# universal_flech.net
KiCad netlist of a schematic drawn in Altium Designer
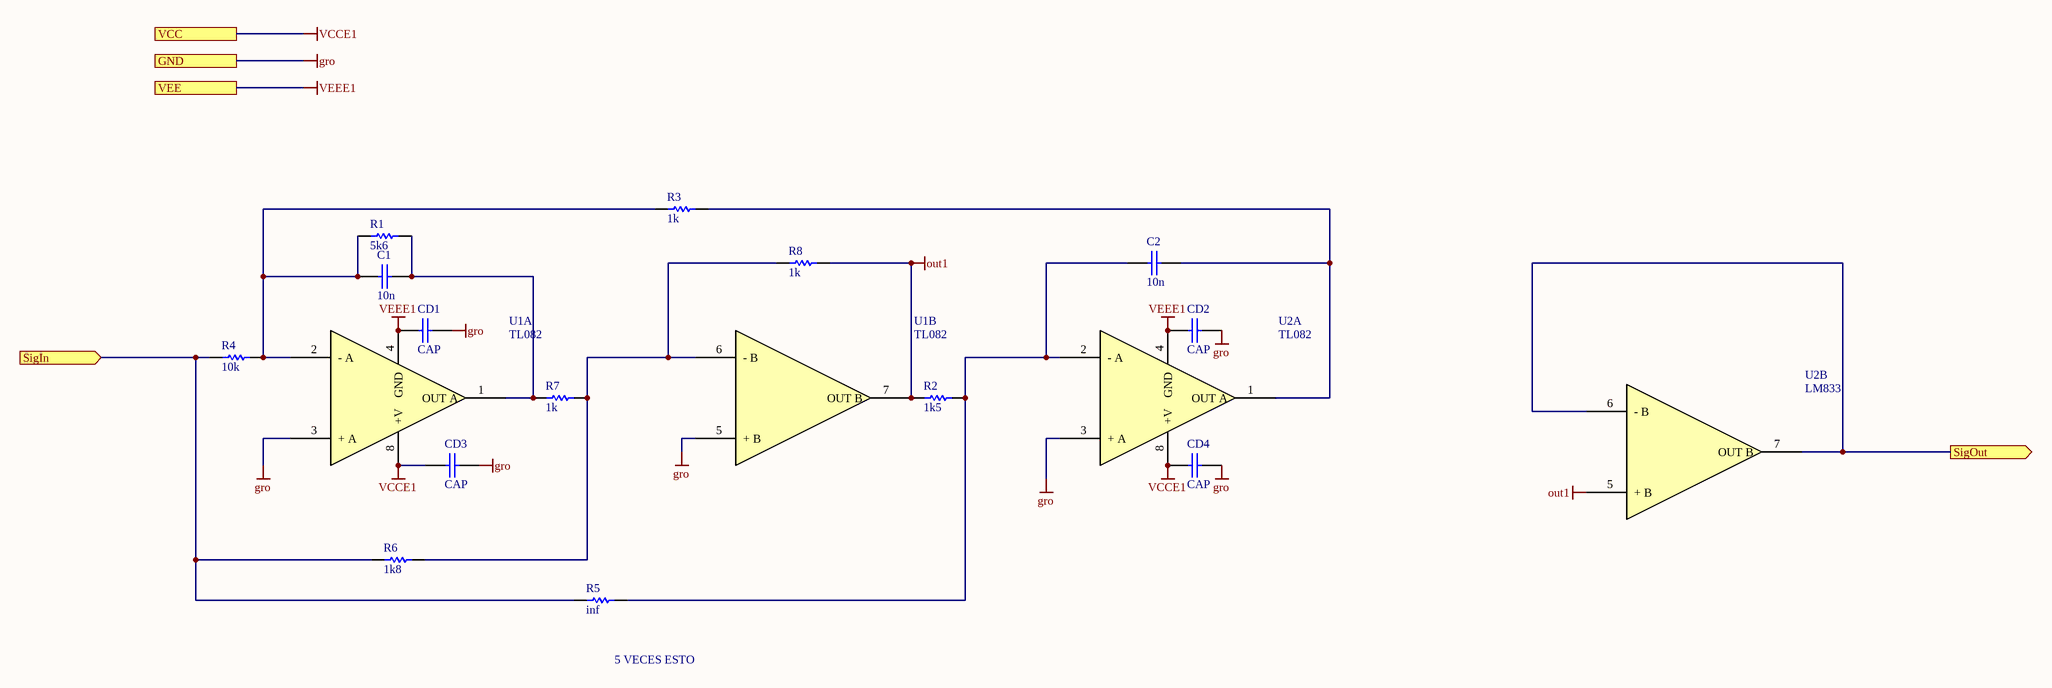
[diagram p0: universal_flech.SchDoc]

(export (version "E")
  (design (tool "Eeschema 10.0.6"))
  (components
    (comp (ref "C1") (value "10n") (footprint "CAP200") (libsource (lib "LIBEBAL") (part "CAP")))
    (comp (ref "C2") (value "10n") (footprint "CAP200") (libsource (lib "LIBEBAL") (part "CAP")))
    (comp (ref "CD1") (value "CAP") (footprint "CAP200") (libsource (lib "LIBEBAL") (part "CAP")))
    (comp (ref "CD2") (value "CAP") (footprint "CAP200") (libsource (lib "LIBEBAL") (part "CAP")))
    (comp (ref "CD3") (value "CAP") (footprint "CAP200") (libsource (lib "LIBEBAL") (part "CAP")))
    (comp (ref "CD4") (value "CAP") (footprint "CAP200") (libsource (lib "LIBEBAL") (part "CAP")))
    (comp (ref "R1") (value "5k6") (footprint "0805") (libsource (lib "LIBEBAL") (part "RES")))
    (comp (ref "R2") (value "1k5") (footprint "0805") (libsource (lib "LIBEBAL") (part "RES")))
    (comp (ref "R3") (value "1k") (footprint "0805") (libsource (lib "LIBEBAL") (part "RES")))
    (comp (ref "R4") (value "10k") (footprint "0805") (libsource (lib "LIBEBAL") (part "RES")))
    (comp (ref "R5") (value "inf") (footprint "0805") (libsource (lib "LIBEBAL") (part "RES")))
    (comp (ref "R6") (value "1k8") (footprint "0805") (libsource (lib "LIBEBAL") (part "RES")))
    (comp (ref "R7") (value "1k") (footprint "0805") (libsource (lib "LIBEBAL") (part "RES")))
    (comp (ref "R8") (value "1k") (footprint "0805") (libsource (lib "LIBEBAL") (part "RES")))
    (comp (ref "U1")
      (value "TL082")
      (footprint "DIP8")
      (description "Dual Audio Operational Amplifier")
      (libsource (lib "LIBEBAL") (part "LM833"))
    )
    (comp (ref "U2")
      (value "TL082")
      (footprint "DIP8")
      (description "Dual Audio Operational Amplifier")
      (libsource (lib "LIBEBAL") (part "LM833"))
    )
  )
  (nets
    (net (code "1") (name "/SigIn") (class "Default")
      (node (ref "R4") (pin "1") (pinfunction "1_1") (pintype "passive"))
      (node (ref "R5") (pin "1") (pinfunction "1_1") (pintype "passive"))
      (node (ref "R6") (pin "1") (pinfunction "1_1") (pintype "passive"))
    )
    (net (code "2") (name "/SigOut") (class "Default")
      (node (ref "U2") (pin "6") (pinfunction "-_B_6") (pintype "passive"))
      (node (ref "U2") (pin "7") (pinfunction "OUT_B_7") (pintype "passive"))
    )
    (net (code "3") (name "Net-(U1A--_A)") (class "Default")
      (node (ref "C1") (pin "1") (pinfunction "1_1") (pintype "passive"))
      (node (ref "R1") (pin "1") (pinfunction "1_1") (pintype "passive"))
      (node (ref "R3") (pin "1") (pinfunction "1_1") (pintype "passive"))
      (node (ref "R4") (pin "2") (pinfunction "2_2") (pintype "passive"))
      (node (ref "U1") (pin "2") (pinfunction "-_A_2") (pintype "passive"))
    )
    (net (code "4") (name "Net-(U1A-OUT_A)") (class "Default")
      (node (ref "C1") (pin "2") (pinfunction "2_2") (pintype "passive"))
      (node (ref "R1") (pin "2") (pinfunction "2_2") (pintype "passive"))
      (node (ref "R7") (pin "1") (pinfunction "1_1") (pintype "passive"))
      (node (ref "U1") (pin "1") (pinfunction "OUT_A_1") (pintype "passive"))
    )
    (net (code "5") (name "Net-(U1B--_B)") (class "Default")
      (node (ref "R6") (pin "2") (pinfunction "2_2") (pintype "passive"))
      (node (ref "R7") (pin "2") (pinfunction "2_2") (pintype "passive"))
      (node (ref "R8") (pin "1") (pinfunction "1_1") (pintype "passive"))
      (node (ref "U1") (pin "6") (pinfunction "-_B_6") (pintype "passive"))
    )
    (net (code "6") (name "Net-(U2A--_A)") (class "Default")
      (node (ref "C2") (pin "1") (pinfunction "1_1") (pintype "passive"))
      (node (ref "R2") (pin "2") (pinfunction "2_2") (pintype "passive"))
      (node (ref "R5") (pin "2") (pinfunction "2_2") (pintype "passive"))
      (node (ref "U2") (pin "2") (pinfunction "-_A_2") (pintype "passive"))
    )
    (net (code "7") (name "Net-(U2A-OUT_A)") (class "Default")
      (node (ref "C2") (pin "2") (pinfunction "2_2") (pintype "passive"))
      (node (ref "R3") (pin "2") (pinfunction "2_2") (pintype "passive"))
      (node (ref "U2") (pin "1") (pinfunction "OUT_A_1") (pintype "passive"))
    )
    (net (code "8") (name "VCCE1") (class "Default")
      (node (ref "CD3") (pin "1") (pinfunction "1_1") (pintype "passive"))
      (node (ref "CD4") (pin "1") (pinfunction "1_1") (pintype "passive"))
      (node (ref "U1") (pin "8") (pinfunction "+V_8") (pintype "passive"))
      (node (ref "U2") (pin "8") (pinfunction "+V_8") (pintype "passive"))
    )
    (net (code "9") (name "VEEE1") (class "Default")
      (node (ref "CD1") (pin "1") (pinfunction "1_1") (pintype "passive"))
      (node (ref "CD2") (pin "1") (pinfunction "1_1") (pintype "passive"))
      (node (ref "U1") (pin "4") (pinfunction "GND_4") (pintype "passive"))
      (node (ref "U2") (pin "4") (pinfunction "GND_4") (pintype "passive"))
    )
    (net (code "10") (name "gro") (class "Default")
      (node (ref "CD1") (pin "2") (pinfunction "2_2") (pintype "passive"))
      (node (ref "CD2") (pin "2") (pinfunction "2_2") (pintype "passive"))
      (node (ref "CD3") (pin "2") (pinfunction "2_2") (pintype "passive"))
      (node (ref "CD4") (pin "2") (pinfunction "2_2") (pintype "passive"))
      (node (ref "U1") (pin "3") (pinfunction "+_A_3") (pintype "passive"))
      (node (ref "U1") (pin "5") (pinfunction "+_B_5") (pintype "passive"))
      (node (ref "U2") (pin "3") (pinfunction "+_A_3") (pintype "passive"))
    )
    (net (code "11") (name "out1") (class "Default")
      (node (ref "R2") (pin "1") (pinfunction "1_1") (pintype "passive"))
      (node (ref "R8") (pin "2") (pinfunction "2_2") (pintype "passive"))
      (node (ref "U1") (pin "7") (pinfunction "OUT_B_7") (pintype "passive"))
      (node (ref "U2") (pin "5") (pinfunction "+_B_5") (pintype "passive"))
    )
  )
)
